# MCU.net
KiCad netlist of a schematic drawn in Altium Designer
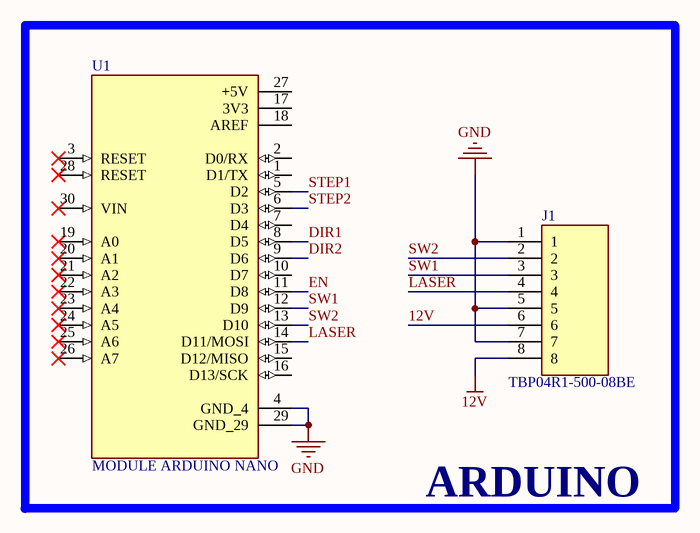
[diagram p0: MCU.SchDoc]

(export (version "E")
  (design (tool "Eeschema 10.0.6"))
  (components
    (comp (ref "J1")
      (value "TBP04R1-500-08BE")
      (footprint "TBP04R1-500-08BE")
      (description "2~24 Poles, Pluggable, Receptacle, Horizontal, 5.0 Pitch, Terminal Block Connector")
      (fields (field (name "MF") "Same Sky"))
      (libsource (lib "JACK") (part "TBP04R1-500-08BE"))
    )
    (comp (ref "U1")
      (value "MODULE ARDUINO NANO")
      (footprint "MODULE ARDUINO NANO")
      (description "Small, complete, and breadboard-friendly board based on the ATmega328 (Arduino Nano 3.x)")
      (fields (field (name "MF") "Arduino") (field (name "MP") "Arduino Nano"))
      (libsource (lib "MODULE") (part "MODULE ARDUINO NANO"))
    )
  )
  (nets
    (net (code "1") (name "/DIR1") (class "Default")
      (node (ref "U1") (pin "8") (pinfunction "D5_8") (pintype "bidirectional"))
    )
    (net (code "2") (name "/DIR2") (class "Default")
      (node (ref "U1") (pin "9") (pinfunction "D6_9") (pintype "bidirectional"))
    )
    (net (code "3") (name "/EN") (class "Default")
      (node (ref "U1") (pin "11") (pinfunction "D8_11") (pintype "bidirectional"))
    )
    (net (code "4") (name "/LASER") (class "Default")
      (node (ref "J1") (pin "4") (pinfunction "4_4") (pintype "passive"))
      (node (ref "U1") (pin "14") (pinfunction "D11/MOSI_14") (pintype "bidirectional"))
    )
    (net (code "5") (name "/STEP1") (class "Default")
      (node (ref "U1") (pin "5") (pinfunction "D2_5") (pintype "bidirectional"))
    )
    (net (code "6") (name "/STEP2") (class "Default")
      (node (ref "U1") (pin "6") (pinfunction "D3_6") (pintype "bidirectional"))
    )
    (net (code "7") (name "/SW1") (class "Default")
      (node (ref "J1") (pin "3") (pinfunction "3_3") (pintype "passive"))
      (node (ref "U1") (pin "12") (pinfunction "D9_12") (pintype "bidirectional"))
    )
    (net (code "8") (name "/SW2") (class "Default")
      (node (ref "J1") (pin "2") (pinfunction "2_2") (pintype "passive"))
      (node (ref "U1") (pin "13") (pinfunction "D10_13") (pintype "bidirectional"))
    )
    (net (code "9") (name "12V") (class "Default")
      (node (ref "J1") (pin "6") (pinfunction "6_6") (pintype "passive"))
      (node (ref "J1") (pin "8") (pinfunction "8_8") (pintype "passive"))
    )
    (net (code "10") (name "GND") (class "Default")
      (node (ref "J1") (pin "1") (pinfunction "1_1") (pintype "passive"))
      (node (ref "J1") (pin "5") (pinfunction "5_5") (pintype "passive"))
      (node (ref "J1") (pin "7") (pinfunction "7_7") (pintype "passive"))
      (node (ref "U1") (pin "29") (pinfunction "GND_29_29") (pintype "power_in"))
      (node (ref "U1") (pin "4") (pinfunction "GND_4_4") (pintype "power_in"))
    )
    (net (code "11") (name "unconnected-(U1-+5V-Pad27)") (class "Default")
      (node (ref "U1") (pin "27") (pinfunction "+5V_27") (pintype "power_in"))
    )
    (net (code "12") (name "unconnected-(U1-3V3-Pad17)") (class "Default")
      (node (ref "U1") (pin "17") (pinfunction "3V3_17") (pintype "power_in"))
    )
    (net (code "13") (name "unconnected-(U1-A0-Pad19)") (class "Default")
      (node (ref "U1") (pin "19") (pinfunction "A0_19") (pintype "input+no_connect"))
    )
    (net (code "14") (name "unconnected-(U1-A1-Pad20)") (class "Default")
      (node (ref "U1") (pin "20") (pinfunction "A1_20") (pintype "input+no_connect"))
    )
    (net (code "15") (name "unconnected-(U1-A2-Pad21)") (class "Default")
      (node (ref "U1") (pin "21") (pinfunction "A2_21") (pintype "input+no_connect"))
    )
    (net (code "16") (name "unconnected-(U1-A3-Pad22)") (class "Default")
      (node (ref "U1") (pin "22") (pinfunction "A3_22") (pintype "input+no_connect"))
    )
    (net (code "17") (name "unconnected-(U1-A4-Pad23)") (class "Default")
      (node (ref "U1") (pin "23") (pinfunction "A4_23") (pintype "input+no_connect"))
    )
    (net (code "18") (name "unconnected-(U1-A5-Pad24)") (class "Default")
      (node (ref "U1") (pin "24") (pinfunction "A5_24") (pintype "input+no_connect"))
    )
    (net (code "19") (name "unconnected-(U1-A6-Pad25)") (class "Default")
      (node (ref "U1") (pin "25") (pinfunction "A6_25") (pintype "input+no_connect"))
    )
    (net (code "20") (name "unconnected-(U1-A7-Pad26)") (class "Default")
      (node (ref "U1") (pin "26") (pinfunction "A7_26") (pintype "input+no_connect"))
    )
    (net (code "21") (name "unconnected-(U1-AREF-Pad18)") (class "Default")
      (node (ref "U1") (pin "18") (pinfunction "AREF_18") (pintype "power_in"))
    )
    (net (code "22") (name "unconnected-(U1-D0{slash}RX-Pad2)") (class "Default")
      (node (ref "U1") (pin "2") (pinfunction "D0/RX_2") (pintype "bidirectional"))
    )
    (net (code "23") (name "unconnected-(U1-D1{slash}TX-Pad1)") (class "Default")
      (node (ref "U1") (pin "1") (pinfunction "D1/TX_1") (pintype "bidirectional"))
    )
    (net (code "24") (name "unconnected-(U1-D4-Pad7)") (class "Default")
      (node (ref "U1") (pin "7") (pinfunction "D4_7") (pintype "bidirectional"))
    )
    (net (code "25") (name "unconnected-(U1-D7-Pad10)") (class "Default")
      (node (ref "U1") (pin "10") (pinfunction "D7_10") (pintype "bidirectional"))
    )
    (net (code "26") (name "unconnected-(U1-D12{slash}MISO-Pad15)") (class "Default")
      (node (ref "U1") (pin "15") (pinfunction "D12/MISO_15") (pintype "bidirectional"))
    )
    (net (code "27") (name "unconnected-(U1-D13{slash}SCK-Pad16)") (class "Default")
      (node (ref "U1") (pin "16") (pinfunction "D13/SCK_16") (pintype "bidirectional"))
    )
    (net (code "28") (name "unconnected-(U1-RESET-Pad3)") (class "Default")
      (node (ref "U1") (pin "3") (pinfunction "RESET_3") (pintype "input+no_connect"))
    )
    (net (code "29") (name "unconnected-(U1-RESET-Pad28)") (class "Default")
      (node (ref "U1") (pin "28") (pinfunction "RESET_28") (pintype "input+no_connect"))
    )
    (net (code "30") (name "unconnected-(U1-VIN-Pad30)") (class "Default")
      (node (ref "U1") (pin "30") (pinfunction "VIN_30") (pintype "input+no_connect"))
    )
  )
)
